# Audio.net
KiCad netlist of a schematic drawn in Altium Designer
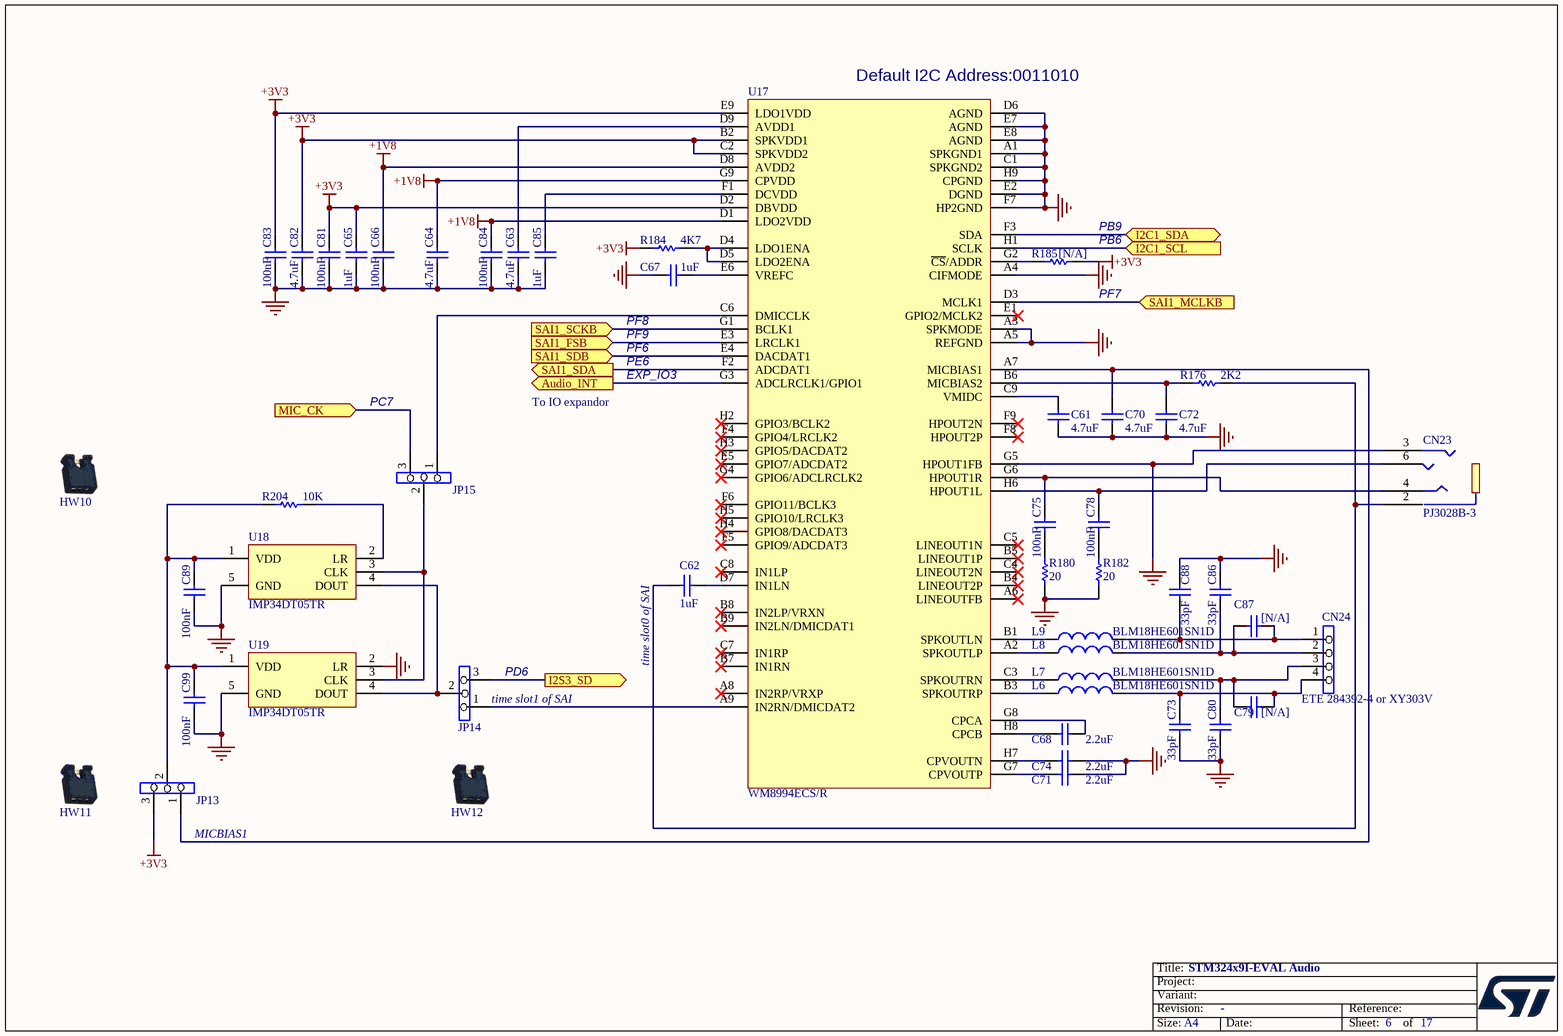
[diagram p0: Audio.SchDoc]

(export (version "E")
  (design (tool "Eeschema 10.0.6"))
  (components
    (comp (ref "C61")
      (value "4.7uF")
      (footprint "0603C")
      (description "Capacitor")
      (fields (field (name "PUBLISHER") "Altium Limited"))
      (libsource (lib "Miscellaneous Devices") (part "Cap"))
    )
    (comp (ref "C62")
      (value "1uF")
      (footprint "0603C")
      (description "Capacitor")
      (fields (field (name "PUBLISHER") "Altium Limited"))
      (libsource (lib "Miscellaneous Devices") (part "CAP"))
    )
    (comp (ref "C63")
      (value "4.7uF")
      (footprint "0603C")
      (description "Capacitor")
      (fields (field (name "PUBLISHER") "Altium Limited"))
      (libsource (lib "Miscellaneous Devices") (part "Cap"))
    )
    (comp (ref "C64")
      (value "4.7uF")
      (footprint "0603C")
      (description "Capacitor")
      (fields (field (name "PUBLISHER") "Altium Limited"))
      (libsource (lib "Miscellaneous Devices") (part "Cap"))
    )
    (comp (ref "C65")
      (value "1uF")
      (footprint "0603C")
      (description "Capacitor")
      (fields (field (name "PUBLISHER") "Altium Limited"))
      (libsource (lib "Miscellaneous Devices") (part "CAP"))
    )
    (comp (ref "C66")
      (value "100nF")
      (footprint "0603C")
      (description "Capacitor")
      (fields (field (name "PUBLISHER") "Altium Limited"))
      (libsource (lib "Miscellaneous Devices") (part "Cap"))
    )
    (comp (ref "C67")
      (value "1uF")
      (footprint "0603C")
      (description "Capacitor")
      (fields (field (name "PUBLISHER") "Altium Limited"))
      (libsource (lib "Miscellaneous Devices") (part "CAP"))
    )
    (comp (ref "C68")
      (value "2.2uF")
      (footprint "0603C")
      (description "Capacitor")
      (fields (field (name "PUBLISHER") "Altium Limited"))
      (libsource (lib "Miscellaneous Devices") (part "CAP"))
    )
    (comp (ref "C70")
      (value "4.7uF")
      (footprint "0603C")
      (description "Capacitor")
      (fields (field (name "PUBLISHER") "Altium Limited"))
      (libsource (lib "Miscellaneous Devices") (part "Cap"))
    )
    (comp (ref "C71")
      (value "2.2uF")
      (footprint "0603C")
      (description "Capacitor")
      (fields (field (name "PUBLISHER") "Altium Limited"))
      (libsource (lib "Miscellaneous Devices") (part "CAP"))
    )
    (comp (ref "C72")
      (value "4.7uF")
      (footprint "0603C")
      (description "Capacitor")
      (fields (field (name "PUBLISHER") "Altium Limited"))
      (libsource (lib "Miscellaneous Devices") (part "Cap"))
    )
    (comp (ref "C73")
      (value "33pF")
      (footprint "0603C")
      (description "Capacitor")
      (fields (field (name "PUBLISHER") "Altium Limited"))
      (libsource (lib "Miscellaneous Devices") (part "Cap"))
    )
    (comp (ref "C74")
      (value "2.2uF")
      (footprint "0603C")
      (description "Capacitor")
      (fields (field (name "PUBLISHER") "Altium Limited"))
      (libsource (lib "Miscellaneous Devices") (part "CAP"))
    )
    (comp (ref "C75")
      (value "100nF")
      (footprint "0603C")
      (description "Capacitor")
      (fields (field (name "PUBLISHER") "Altium Limited"))
      (libsource (lib "Miscellaneous Devices") (part "Cap"))
    )
    (comp (ref "C78")
      (value "100nF")
      (footprint "0603C")
      (description "Capacitor")
      (fields (field (name "PUBLISHER") "Altium Limited"))
      (libsource (lib "Miscellaneous Devices") (part "Cap"))
    )
    (comp (ref "C79")
      (value "[N/A]")
      (footprint "0603C")
      (description "Capacitor")
      (fields (field (name "PUBLISHER") "Altium Limited"))
      (libsource (lib "Miscellaneous Devices") (part "Cap"))
    )
    (comp (ref "C80")
      (value "33pF")
      (footprint "0603C")
      (description "Capacitor")
      (fields (field (name "PUBLISHER") "Altium Limited"))
      (libsource (lib "Miscellaneous Devices") (part "Cap"))
    )
    (comp (ref "C81")
      (value "100nF")
      (footprint "0603C")
      (description "Capacitor")
      (fields (field (name "PUBLISHER") "Altium Limited"))
      (libsource (lib "Miscellaneous Devices") (part "Cap"))
    )
    (comp (ref "C82")
      (value "4.7uF")
      (footprint "0603C")
      (description "Capacitor")
      (fields (field (name "PUBLISHER") "Altium Limited"))
      (libsource (lib "Miscellaneous Devices") (part "Cap"))
    )
    (comp (ref "C83")
      (value "100nF")
      (footprint "0603C")
      (description "Capacitor")
      (fields (field (name "PUBLISHER") "Altium Limited"))
      (libsource (lib "Miscellaneous Devices") (part "Cap"))
    )
    (comp (ref "C84")
      (value "100nF")
      (footprint "0603C")
      (description "Capacitor")
      (fields (field (name "PUBLISHER") "Altium Limited"))
      (libsource (lib "Miscellaneous Devices") (part "Cap"))
    )
    (comp (ref "C85")
      (value "1uF")
      (footprint "0603C")
      (description "Capacitor")
      (fields (field (name "PUBLISHER") "Altium Limited"))
      (libsource (lib "Miscellaneous Devices") (part "CAP"))
    )
    (comp (ref "C86")
      (value "33pF")
      (footprint "0603C")
      (description "Capacitor")
      (fields (field (name "PUBLISHER") "Altium Limited"))
      (libsource (lib "Miscellaneous Devices") (part "Cap"))
    )
    (comp (ref "C87")
      (value "[N/A]")
      (footprint "0603C")
      (description "Capacitor")
      (fields (field (name "PUBLISHER") "Altium Limited"))
      (libsource (lib "Miscellaneous Devices") (part "Cap"))
    )
    (comp (ref "C88")
      (value "33pF")
      (footprint "0603C")
      (description "Capacitor")
      (fields (field (name "PUBLISHER") "Altium Limited"))
      (libsource (lib "Miscellaneous Devices") (part "Cap"))
    )
    (comp (ref "C89")
      (value "100nF")
      (footprint "0603C")
      (description "Capacitor")
      (fields (field (name "PUBLISHER") "Altium Limited"))
      (libsource (lib "Miscellaneous Devices") (part "Cap"))
    )
    (comp (ref "C99")
      (value "100nF")
      (footprint "0603C")
      (description "Capacitor")
      (fields (field (name "PUBLISHER") "Altium Limited"))
      (libsource (lib "Miscellaneous Devices") (part "Cap"))
    )
    (comp (ref "CN23") (value "PJ3028B-3") (footprint "PJ3028B") (libsource (lib "MB786") (part "PJ3028B-3")))
    (comp (ref "CN24")
      (value "ETE 284392-4 or XY303V")
      (footprint "BUCHANAN_284392-4")
      (description "ETE 284392-4")
      (libsource (lib "mb1045") (part "ETE 284392-4 or XY303V"))
    )
    (comp (ref "HW10") (value "JUMPER_OPEN") (libsource (lib "mb1045") (part "JUMPER_OPEN")))
    (comp (ref "HW11") (value "JUMPER_OPEN") (libsource (lib "mb1045") (part "JUMPER_OPEN")))
    (comp (ref "HW12") (value "JUMPER_OPEN") (libsource (lib "mb1045") (part "JUMPER_OPEN")))
    (comp (ref "JP13") (value "~") (footprint "SIP3") (libsource (lib "STR910_SCHLIB") (part "Jumper3")))
    (comp (ref "JP14") (value "~") (footprint "SIP3") (libsource (lib "STR910_SCHLIB") (part "Jumper3")))
    (comp (ref "JP15") (value "~") (footprint "SIP3") (libsource (lib "STR910_SCHLIB") (part "Jumper3")))
    (comp (ref "L6")
      (value "BLM18HE601SN1D")
      (footprint "0603L")
      (description "Inductor")
      (fields (field (name "PUBLISHER") "Altium Limited"))
      (libsource (lib "Miscellaneous Devices") (part "Inductor"))
    )
    (comp (ref "L7")
      (value "BLM18HE601SN1D")
      (footprint "0603L")
      (description "Inductor")
      (fields (field (name "PUBLISHER") "Altium Limited"))
      (libsource (lib "Miscellaneous Devices") (part "Inductor"))
    )
    (comp (ref "L8")
      (value "BLM18HE601SN1D")
      (footprint "0603L")
      (description "Inductor")
      (fields (field (name "PUBLISHER") "Altium Limited"))
      (libsource (lib "Miscellaneous Devices") (part "Inductor"))
    )
    (comp (ref "L9")
      (value "BLM18HE601SN1D")
      (footprint "0603L")
      (description "Inductor")
      (fields (field (name "PUBLISHER") "Altium Limited"))
      (libsource (lib "Miscellaneous Devices") (part "Inductor"))
    )
    (comp (ref "R176")
      (value "2K2")
      (footprint "0603R")
      (description "Resistor")
      (fields (field (name "PUBLISHER") "Altium Limited"))
      (libsource (lib "Miscellaneous Devices") (part "Res1"))
    )
    (comp (ref "R180")
      (value "20")
      (footprint "0603R")
      (description "Resistor")
      (fields (field (name "PUBLISHER") "Altium Limited"))
      (libsource (lib "Miscellaneous Devices") (part "Res1"))
    )
    (comp (ref "R182")
      (value "20")
      (footprint "0603R")
      (description "Resistor")
      (fields (field (name "PUBLISHER") "Altium Limited"))
      (libsource (lib "Miscellaneous Devices") (part "Res1"))
    )
    (comp (ref "R184")
      (value "4K7")
      (footprint "0603R")
      (description "Resistor")
      (fields (field (name "PUBLISHER") "Altium Limited"))
      (libsource (lib "Miscellaneous Devices") (part "Res1"))
    )
    (comp (ref "R185")
      (value "[N/A]")
      (footprint "0603R")
      (description "Resistor")
      (fields (field (name "PUBLISHER") "Altium Limited"))
      (libsource (lib "Miscellaneous Devices") (part "Res1"))
    )
    (comp (ref "R204")
      (value "10K")
      (footprint "0603R")
      (description "Resistor")
      (fields (field (name "PUBLISHER") "Altium Limited"))
      (libsource (lib "Miscellaneous Devices") (part "Res1"))
    )
    (comp (ref "U17")
      (value "WM8994ECS/R")
      (footprint "BGA72_0R5_4R5X4")
      (libsource (lib "mb1045") (part "WM8994ECS/R"))
    )
    (comp (ref "U18")
      (value "IMP34DT05TR")
      (footprint "MP34DT01TR")
      (description "MEMS audio sensor omnidirectional digital microphone for industrial applications")
      (fields (field (name "PUBLISHER") "Altium Limited"))
      (libsource (lib "mb1045") (part "MP34DT01TR"))
    )
    (comp (ref "U19")
      (value "IMP34DT05TR")
      (footprint "MP34DT01TR")
      (description "MEMS audio sensor omnidirectional digital microphone for industrial applications")
      (fields (field (name "PUBLISHER") "Altium Limited"))
      (libsource (lib "mb1045") (part "MP34DT01TR"))
    )
  )
  (nets
    (net (code "1") (name "+1V8") (class "Default")
      (node (ref "C64") (pin "1") (pinfunction "1_1") (pintype "passive"))
      (node (ref "C66") (pin "1") (pinfunction "1_1") (pintype "passive"))
      (node (ref "C84") (pin "1") (pinfunction "1_1") (pintype "passive"))
      (node (ref "U17") (pin "D1") (pinfunction "LDO2VDD_D1") (pintype "passive"))
      (node (ref "U17") (pin "D8") (pinfunction "AVDD2_D8") (pintype "passive"))
      (node (ref "U17") (pin "G9") (pinfunction "CPVDD_G9") (pintype "passive"))
    )
    (net (code "2") (name "+3V3") (class "Default")
      (node (ref "C65") (pin "1") (pinfunction "1_1") (pintype "passive"))
      (node (ref "C81") (pin "1") (pinfunction "1_1") (pintype "passive"))
      (node (ref "C82") (pin "1") (pinfunction "1_1") (pintype "passive"))
      (node (ref "C83") (pin "1") (pinfunction "1_1") (pintype "passive"))
      (node (ref "JP13") (pin "3") (pintype "passive"))
      (node (ref "R184") (pin "2") (pinfunction "2_2") (pintype "passive"))
      (node (ref "R185") (pin "1") (pinfunction "1_1") (pintype "passive"))
      (node (ref "U17") (pin "B2") (pinfunction "SPKVDD1_B2") (pintype "passive"))
      (node (ref "U17") (pin "C2") (pinfunction "SPKVDD2_C2") (pintype "passive"))
      (node (ref "U17") (pin "D2") (pinfunction "DBVDD_D2") (pintype "passive"))
      (node (ref "U17") (pin "E9") (pinfunction "LDO1VDD_E9") (pintype "passive"))
    )
    (net (code "3") (name "/Audio_INT") (class "Default")
      (node (ref "U17") (pin "G3") (pinfunction "ADCLRCLK1/GPIO1_G3") (pintype "passive"))
    )
    (net (code "4") (name "/I2C1_SCL") (class "Default")
      (node (ref "U17") (pin "H1") (pinfunction "SCLK_H1") (pintype "passive"))
    )
    (net (code "5") (name "/I2C1_SDA") (class "Default")
      (node (ref "U17") (pin "F3") (pinfunction "SDA_F3") (pintype "passive"))
    )
    (net (code "6") (name "/I2S3_SD") (class "Default") (node (ref "JP14") (pin "3") (pintype "passive")))
    (net (code "7") (name "/MIC_CK") (class "Default") (node (ref "JP15") (pin "3") (pintype "passive")))
    (net (code "8") (name "/SAI1_FSB") (class "Default")
      (node (ref "U17") (pin "E3") (pinfunction "LRCLK1_E3") (pintype "passive"))
    )
    (net (code "9") (name "/SAI1_MCLKB") (class "Default")
      (node (ref "U17") (pin "D3") (pinfunction "MCLK1_D3") (pintype "passive"))
    )
    (net (code "10") (name "/SAI1_SCKB") (class "Default")
      (node (ref "U17") (pin "G1") (pinfunction "BCLK1_G1") (pintype "passive"))
    )
    (net (code "11") (name "/SAI1_SDA") (class "Default")
      (node (ref "U17") (pin "F2") (pinfunction "ADCDAT1_F2") (pintype "passive"))
    )
    (net (code "12") (name "/SAI1_SDB") (class "Default")
      (node (ref "U17") (pin "E4") (pinfunction "DACDAT1_E4") (pintype "passive"))
    )
    (net (code "13") (name "GND") (class "Default")
      (node (ref "C61") (pin "1") (pinfunction "1_1") (pintype "passive"))
      (node (ref "C63") (pin "2") (pinfunction "2_2") (pintype "passive"))
      (node (ref "C64") (pin "2") (pinfunction "2_2") (pintype "passive"))
      (node (ref "C65") (pin "2") (pinfunction "2_2") (pintype "passive"))
      (node (ref "C66") (pin "2") (pinfunction "2_2") (pintype "passive"))
      (node (ref "C67") (pin "2") (pinfunction "2_2") (pintype "passive"))
      (node (ref "C70") (pin "1") (pinfunction "1_1") (pintype "passive"))
      (node (ref "C71") (pin "2") (pinfunction "2_2") (pintype "passive"))
      (node (ref "C72") (pin "1") (pinfunction "1_1") (pintype "passive"))
      (node (ref "C73") (pin "2") (pinfunction "2_2") (pintype "passive"))
      (node (ref "C74") (pin "2") (pinfunction "2_2") (pintype "passive"))
      (node (ref "C80") (pin "2") (pinfunction "2_2") (pintype "passive"))
      (node (ref "C81") (pin "2") (pinfunction "2_2") (pintype "passive"))
      (node (ref "C82") (pin "2") (pinfunction "2_2") (pintype "passive"))
      (node (ref "C83") (pin "2") (pinfunction "2_2") (pintype "passive"))
      (node (ref "C84") (pin "2") (pinfunction "2_2") (pintype "passive"))
      (node (ref "C85") (pin "2") (pinfunction "2_2") (pintype "passive"))
      (node (ref "C86") (pin "1") (pinfunction "1_1") (pintype "passive"))
      (node (ref "C88") (pin "1") (pinfunction "1_1") (pintype "passive"))
      (node (ref "C89") (pin "2") (pinfunction "2_2") (pintype "passive"))
      (node (ref "C99") (pin "2") (pinfunction "2_2") (pintype "passive"))
      (node (ref "CN23") (pin "3") (pintype "passive"))
      (node (ref "R180") (pin "2") (pinfunction "2_2") (pintype "passive"))
      (node (ref "R182") (pin "2") (pinfunction "2_2") (pintype "passive"))
      (node (ref "U17") (pin "A1") (pinfunction "SPKGND1_A1") (pintype "passive"))
      (node (ref "U17") (pin "A3") (pinfunction "SPKMODE_A3") (pintype "passive"))
      (node (ref "U17") (pin "A4") (pinfunction "CIFMODE_A4") (pintype "passive"))
      (node (ref "U17") (pin "A5") (pinfunction "REFGND_A5") (pintype "passive"))
      (node (ref "U17") (pin "C1") (pinfunction "SPKGND2_C1") (pintype "passive"))
      (node (ref "U17") (pin "D6") (pinfunction "AGND_D6") (pintype "passive"))
      (node (ref "U17") (pin "E2") (pinfunction "DGND_E2") (pintype "passive"))
      (node (ref "U17") (pin "E7") (pinfunction "AGND_E7") (pintype "passive"))
      (node (ref "U17") (pin "E8") (pinfunction "AGND_E8") (pintype "passive"))
      (node (ref "U17") (pin "F7") (pinfunction "HP2GND_F7") (pintype "passive"))
      (node (ref "U17") (pin "G5") (pinfunction "HPOUT1FB_G5") (pintype "passive"))
      (node (ref "U17") (pin "H9") (pinfunction "CPGND_H9") (pintype "passive"))
      (node (ref "U18") (pin "5") (pinfunction "GND_5") (pintype "passive"))
      (node (ref "U19") (pin "2") (pinfunction "LR_2") (pintype "passive"))
      (node (ref "U19") (pin "5") (pinfunction "GND_5") (pintype "passive"))
    )
    (net (code "14") (name "Net-(C62-Pad2)") (class "Default")
      (node (ref "C62") (pin "2") (pinfunction "2_2") (pintype "passive"))
      (node (ref "CN23") (pin "2") (pintype "passive"))
      (node (ref "R176") (pin "1") (pinfunction "1_1") (pintype "passive"))
    )
    (net (code "15") (name "Net-(C73-Pad1)") (class "Default")
      (node (ref "C73") (pin "1") (pinfunction "1_1") (pintype "passive"))
      (node (ref "C79") (pin "2") (pinfunction "2_2") (pintype "passive"))
      (node (ref "CN24") (pin "4") (pintype "passive"))
      (node (ref "L6") (pin "2") (pinfunction "2_2") (pintype "passive"))
    )
    (net (code "16") (name "Net-(C75-Pad2)") (class "Default")
      (node (ref "C75") (pin "2") (pinfunction "2_2") (pintype "passive"))
      (node (ref "R180") (pin "1") (pinfunction "1_1") (pintype "passive"))
    )
    (net (code "17") (name "Net-(C78-Pad2)") (class "Default")
      (node (ref "C78") (pin "2") (pinfunction "2_2") (pintype "passive"))
      (node (ref "R182") (pin "1") (pinfunction "1_1") (pintype "passive"))
    )
    (net (code "18") (name "Net-(C79-Pad1)") (class "Default")
      (node (ref "C79") (pin "1") (pinfunction "1_1") (pintype "passive"))
      (node (ref "C80") (pin "1") (pinfunction "1_1") (pintype "passive"))
      (node (ref "CN24") (pin "3") (pintype "passive"))
      (node (ref "L7") (pin "2") (pinfunction "2_2") (pintype "passive"))
    )
    (net (code "19") (name "Net-(C86-Pad2)") (class "Default")
      (node (ref "C86") (pin "2") (pinfunction "2_2") (pintype "passive"))
      (node (ref "C87") (pin "1") (pinfunction "1_1") (pintype "passive"))
      (node (ref "CN24") (pin "2") (pintype "passive"))
      (node (ref "L8") (pin "2") (pinfunction "2_2") (pintype "passive"))
    )
    (net (code "20") (name "Net-(C87-Pad2)") (class "Default")
      (node (ref "C87") (pin "2") (pinfunction "2_2") (pintype "passive"))
      (node (ref "C88") (pin "2") (pinfunction "2_2") (pintype "passive"))
      (node (ref "CN24") (pin "1") (pintype "passive"))
      (node (ref "L9") (pin "2") (pinfunction "2_2") (pintype "passive"))
    )
    (net (code "21") (name "Net-(U17-AVDD1)") (class "Default")
      (node (ref "C63") (pin "1") (pinfunction "1_1") (pintype "passive"))
      (node (ref "U17") (pin "D9") (pinfunction "AVDD1_D9") (pintype "passive"))
    )
    (net (code "22") (name "Net-(U17-CPCA)") (class "Default")
      (node (ref "C68") (pin "2") (pinfunction "2_2") (pintype "passive"))
      (node (ref "U17") (pin "G8") (pinfunction "CPCA_G8") (pintype "passive"))
    )
    (net (code "23") (name "Net-(U17-CPCB)") (class "Default")
      (node (ref "C68") (pin "1") (pinfunction "1_1") (pintype "passive"))
      (node (ref "U17") (pin "H8") (pinfunction "CPCB_H8") (pintype "passive"))
    )
    (net (code "24") (name "Net-(U17-CPVOUTN)") (class "Default")
      (node (ref "C74") (pin "1") (pinfunction "1_1") (pintype "passive"))
      (node (ref "U17") (pin "H7") (pinfunction "CPVOUTN_H7") (pintype "passive"))
    )
    (net (code "25") (name "Net-(U17-CPVOUTP)") (class "Default")
      (node (ref "C71") (pin "1") (pinfunction "1_1") (pintype "passive"))
      (node (ref "U17") (pin "G7") (pinfunction "CPVOUTP_G7") (pintype "passive"))
    )
    (net (code "26") (name "Net-(U17-DCVDD)") (class "Default")
      (node (ref "C85") (pin "1") (pinfunction "1_1") (pintype "passive"))
      (node (ref "U17") (pin "F1") (pinfunction "DCVDD_F1") (pintype "passive"))
    )
    (net (code "27") (name "Net-(U17-DMICCLK)") (class "Default")
      (node (ref "JP15") (pin "1") (pintype "passive"))
      (node (ref "U17") (pin "C6") (pinfunction "DMICCLK_C6") (pintype "passive"))
    )
    (net (code "28") (name "Net-(U17-HPOUT1L)") (class "Default")
      (node (ref "C78") (pin "1") (pinfunction "1_1") (pintype "passive"))
      (node (ref "CN23") (pin "6") (pintype "passive"))
      (node (ref "U17") (pin "H6") (pinfunction "HPOUT1L_H6") (pintype "passive"))
    )
    (net (code "29") (name "Net-(U17-HPOUT1R)") (class "Default")
      (node (ref "C75") (pin "1") (pinfunction "1_1") (pintype "passive"))
      (node (ref "CN23") (pin "4") (pintype "passive"))
      (node (ref "U17") (pin "G6") (pinfunction "HPOUT1R_G6") (pintype "passive"))
    )
    (net (code "30") (name "Net-(U17-IN1LN)") (class "Default")
      (node (ref "C62") (pin "1") (pinfunction "1_1") (pintype "passive"))
      (node (ref "U17") (pin "D7") (pinfunction "IN1LN_D7") (pintype "passive"))
    )
    (net (code "31") (name "Net-(U17-IN2RN{slash}DMICDAT2)") (class "Default")
      (node (ref "JP14") (pin "1") (pintype "passive"))
      (node (ref "U17") (pin "A9") (pinfunction "IN2RN/DMICDAT2_A9") (pintype "passive"))
    )
    (net (code "32") (name "Net-(U17-LDO1ENA)") (class "Default")
      (node (ref "R184") (pin "1") (pinfunction "1_1") (pintype "passive"))
      (node (ref "U17") (pin "D4") (pinfunction "LDO1ENA_D4") (pintype "passive"))
      (node (ref "U17") (pin "D5") (pinfunction "LDO2ENA_D5") (pintype "passive"))
    )
    (net (code "33") (name "Net-(U17-MICBIAS1)") (class "Default")
      (node (ref "C70") (pin "2") (pinfunction "2_2") (pintype "passive"))
      (node (ref "JP13") (pin "1") (pintype "passive"))
      (node (ref "U17") (pin "A7") (pinfunction "MICBIAS1_A7") (pintype "passive"))
    )
    (net (code "34") (name "Net-(U17-MICBIAS2)") (class "Default")
      (node (ref "C72") (pin "2") (pinfunction "2_2") (pintype "passive"))
      (node (ref "R176") (pin "2") (pinfunction "2_2") (pintype "passive"))
      (node (ref "U17") (pin "B6") (pinfunction "MICBIAS2_B6") (pintype "passive"))
    )
    (net (code "35") (name "Net-(U17-SPKOUTLN)") (class "Default")
      (node (ref "L9") (pin "1") (pinfunction "1_1") (pintype "passive"))
      (node (ref "U17") (pin "B1") (pinfunction "SPKOUTLN_B1") (pintype "passive"))
    )
    (net (code "36") (name "Net-(U17-SPKOUTLP)") (class "Default")
      (node (ref "L8") (pin "1") (pinfunction "1_1") (pintype "passive"))
      (node (ref "U17") (pin "A2") (pinfunction "SPKOUTLP_A2") (pintype "passive"))
    )
    (net (code "37") (name "Net-(U17-SPKOUTRN)") (class "Default")
      (node (ref "L7") (pin "1") (pinfunction "1_1") (pintype "passive"))
      (node (ref "U17") (pin "C3") (pinfunction "SPKOUTRN_C3") (pintype "passive"))
    )
    (net (code "38") (name "Net-(U17-SPKOUTRP)") (class "Default")
      (node (ref "L6") (pin "1") (pinfunction "1_1") (pintype "passive"))
      (node (ref "U17") (pin "B3") (pinfunction "SPKOUTRP_B3") (pintype "passive"))
    )
    (net (code "39") (name "Net-(U17-VMIDC)") (class "Default")
      (node (ref "C61") (pin "2") (pinfunction "2_2") (pintype "passive"))
      (node (ref "U17") (pin "C9") (pinfunction "VMIDC_C9") (pintype "passive"))
    )
    (net (code "40") (name "Net-(U17-VREFC)") (class "Default")
      (node (ref "C67") (pin "1") (pinfunction "1_1") (pintype "passive"))
      (node (ref "U17") (pin "E6") (pinfunction "VREFC_E6") (pintype "passive"))
    )
    (net (code "41") (name "Net-(U17-~{CS}{slash}ADDR)") (class "Default")
      (node (ref "R185") (pin "2") (pinfunction "2_2") (pintype "passive"))
      (node (ref "U17") (pin "G2") (pinfunction "~{CS}/ADDR_G2") (pintype "passive"))
    )
    (net (code "42") (name "Net-(U18-CLK)") (class "Default")
      (node (ref "JP15") (pin "2") (pintype "passive"))
      (node (ref "U18") (pin "3") (pinfunction "CLK_3") (pintype "passive"))
      (node (ref "U19") (pin "3") (pinfunction "CLK_3") (pintype "passive"))
    )
    (net (code "43") (name "Net-(U18-DOUT)") (class "Default")
      (node (ref "JP14") (pin "2") (pintype "passive"))
      (node (ref "U18") (pin "4") (pinfunction "DOUT_4") (pintype "passive"))
      (node (ref "U19") (pin "4") (pinfunction "DOUT_4") (pintype "passive"))
    )
    (net (code "44") (name "Net-(U18-LR)") (class "Default")
      (node (ref "R204") (pin "1") (pinfunction "1_1") (pintype "passive"))
      (node (ref "U18") (pin "2") (pinfunction "LR_2") (pintype "passive"))
    )
    (net (code "45") (name "Net-(U18-VDD)") (class "Default")
      (node (ref "C89") (pin "1") (pinfunction "1_1") (pintype "passive"))
      (node (ref "C99") (pin "1") (pinfunction "1_1") (pintype "passive"))
      (node (ref "JP13") (pin "2") (pintype "passive"))
      (node (ref "R204") (pin "2") (pinfunction "2_2") (pintype "passive"))
      (node (ref "U18") (pin "1") (pinfunction "VDD_1") (pintype "passive"))
      (node (ref "U19") (pin "1") (pinfunction "VDD_1") (pintype "passive"))
    )
    (net (code "46") (name "unconnected-(U17-GPIO2{slash}MCLK2-PadE1)") (class "Default")
      (node (ref "U17") (pin "E1") (pinfunction "GPIO2/MCLK2_E1") (pintype "passive+no_connect"))
    )
    (net (code "47") (name "unconnected-(U17-GPIO3{slash}BCLK2-PadH2)") (class "Default")
      (node (ref "U17") (pin "H2") (pinfunction "GPIO3/BCLK2_H2") (pintype "passive+no_connect"))
    )
    (net (code "48") (name "unconnected-(U17-GPIO4{slash}LRCLK2-PadF4)") (class "Default")
      (node (ref "U17") (pin "F4") (pinfunction "GPIO4/LRCLK2_F4") (pintype "passive+no_connect"))
    )
    (net (code "49") (name "unconnected-(U17-GPIO5{slash}DACDAT2-PadH3)") (class "Default")
      (node (ref "U17") (pin "H3") (pinfunction "GPIO5/DACDAT2_H3") (pintype "passive+no_connect"))
    )
    (net (code "50") (name "unconnected-(U17-GPIO6{slash}ADCLRCLK2-PadG4)") (class "Default")
      (node (ref "U17") (pin "G4") (pinfunction "GPIO6/ADCLRCLK2_G4") (pintype "passive+no_connect"))
    )
    (net (code "51") (name "unconnected-(U17-GPIO7{slash}ADCDAT2-PadE5)") (class "Default")
      (node (ref "U17") (pin "E5") (pinfunction "GPIO7/ADCDAT2_E5") (pintype "passive+no_connect"))
    )
    (net (code "52") (name "unconnected-(U17-GPIO8{slash}DACDAT3-PadH4)") (class "Default")
      (node (ref "U17") (pin "H4") (pinfunction "GPIO8/DACDAT3_H4") (pintype "passive+no_connect"))
    )
    (net (code "53") (name "unconnected-(U17-GPIO9{slash}ADCDAT3-PadF5)") (class "Default")
      (node (ref "U17") (pin "F5") (pinfunction "GPIO9/ADCDAT3_F5") (pintype "passive+no_connect"))
    )
    (net (code "54") (name "unconnected-(U17-GPIO10{slash}LRCLK3-PadH5)") (class "Default")
      (node (ref "U17") (pin "H5") (pinfunction "GPIO10/LRCLK3_H5") (pintype "passive+no_connect"))
    )
    (net (code "55") (name "unconnected-(U17-GPIO11{slash}BCLK3-PadF6)") (class "Default")
      (node (ref "U17") (pin "F6") (pinfunction "GPIO11/BCLK3_F6") (pintype "passive+no_connect"))
    )
    (net (code "56") (name "unconnected-(U17-HPOUT2N-PadF9)") (class "Default")
      (node (ref "U17") (pin "F9") (pinfunction "HPOUT2N_F9") (pintype "passive+no_connect"))
    )
    (net (code "57") (name "unconnected-(U17-HPOUT2P-PadF8)") (class "Default")
      (node (ref "U17") (pin "F8") (pinfunction "HPOUT2P_F8") (pintype "passive+no_connect"))
    )
    (net (code "58") (name "unconnected-(U17-IN1LP-PadC8)") (class "Default")
      (node (ref "U17") (pin "C8") (pinfunction "IN1LP_C8") (pintype "passive+no_connect"))
    )
    (net (code "59") (name "unconnected-(U17-IN1RN-PadB7)") (class "Default")
      (node (ref "U17") (pin "B7") (pinfunction "IN1RN_B7") (pintype "passive+no_connect"))
    )
    (net (code "60") (name "unconnected-(U17-IN1RP-PadC7)") (class "Default")
      (node (ref "U17") (pin "C7") (pinfunction "IN1RP_C7") (pintype "passive+no_connect"))
    )
    (net (code "61") (name "unconnected-(U17-IN2LN{slash}DMICDAT1-PadB9)") (class "Default")
      (node (ref "U17") (pin "B9") (pinfunction "IN2LN/DMICDAT1_B9") (pintype "passive+no_connect"))
    )
    (net (code "62") (name "unconnected-(U17-IN2LP{slash}VRXN-PadB8)") (class "Default")
      (node (ref "U17") (pin "B8") (pinfunction "IN2LP/VRXN_B8") (pintype "passive+no_connect"))
    )
    (net (code "63") (name "unconnected-(U17-IN2RP{slash}VRXP-PadA8)") (class "Default")
      (node (ref "U17") (pin "A8") (pinfunction "IN2RP/VRXP_A8") (pintype "passive+no_connect"))
    )
    (net (code "64") (name "unconnected-(U17-LINEOUT1N-PadC5)") (class "Default")
      (node (ref "U17") (pin "C5") (pinfunction "LINEOUT1N_C5") (pintype "passive+no_connect"))
    )
    (net (code "65") (name "unconnected-(U17-LINEOUT1P-PadB5)") (class "Default")
      (node (ref "U17") (pin "B5") (pinfunction "LINEOUT1P_B5") (pintype "passive+no_connect"))
    )
    (net (code "66") (name "unconnected-(U17-LINEOUT2N-PadC4)") (class "Default")
      (node (ref "U17") (pin "C4") (pinfunction "LINEOUT2N_C4") (pintype "passive+no_connect"))
    )
    (net (code "67") (name "unconnected-(U17-LINEOUT2P-PadB4)") (class "Default")
      (node (ref "U17") (pin "B4") (pinfunction "LINEOUT2P_B4") (pintype "passive+no_connect"))
    )
    (net (code "68") (name "unconnected-(U17-LINEOUTFB-PadA6)") (class "Default")
      (node (ref "U17") (pin "A6") (pinfunction "LINEOUTFB_A6") (pintype "passive+no_connect"))
    )
  )
)
